# SCH_HACK-HOLIDAY_2025-01-30.net
KiCad netlist of a schematic drawn in EasyEDA
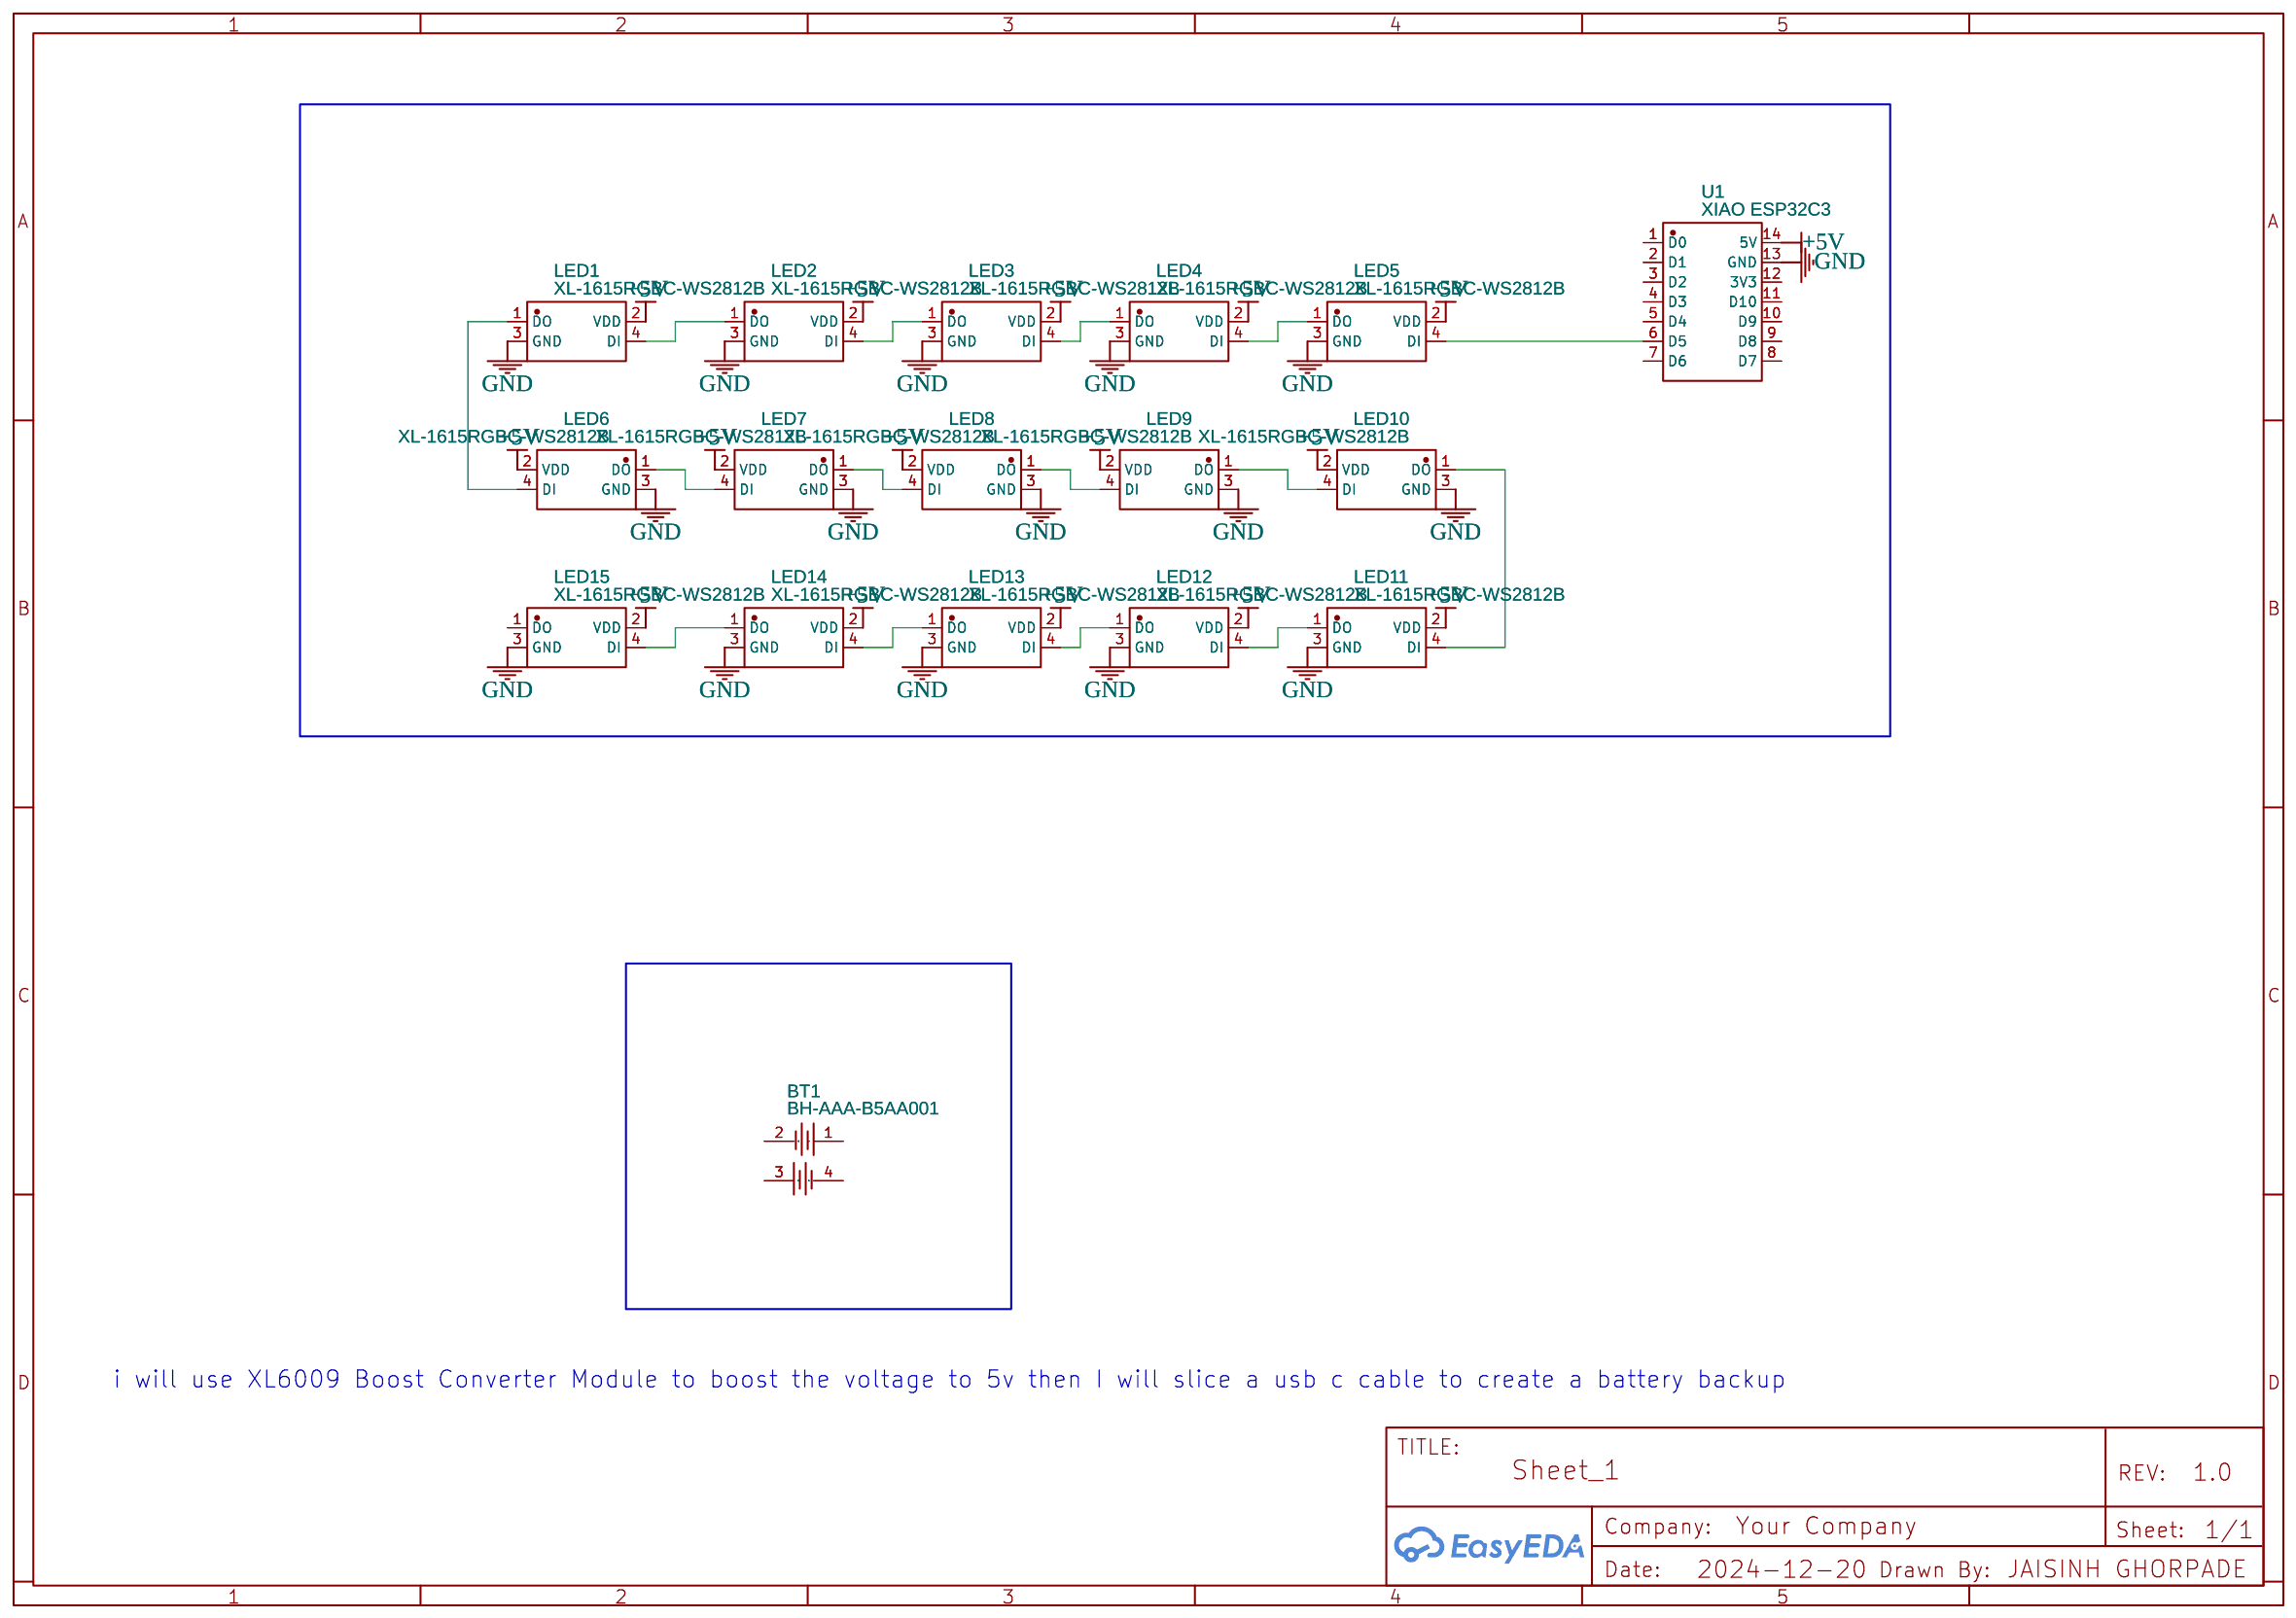
[diagram p0: schematic sheet]

(export (version "E")
  (design (tool "Eeschema 10.0.6"))
  (components
    (comp (ref "BT1")
      (value "BH-AAA-B5AA001")
      (fields (field (name "Manufacturer") "MYOUNG(美阳)"))
      (libsource (lib "") (part "BH-AAA-B5AA001"))
    )
    (comp (ref "LED1")
      (value "XL-1615RGBC-WS2812B")
      (fields (field (name "Manufacturer") "XINGLIGHT(成兴光)"))
      (libsource (lib "") (part "XL-1615RGBC-WS2812B"))
    )
    (comp (ref "LED2")
      (value "XL-1615RGBC-WS2812B")
      (fields (field (name "Manufacturer") "XINGLIGHT(成兴光)"))
      (libsource (lib "") (part "XL-1615RGBC-WS2812B"))
    )
    (comp (ref "LED3")
      (value "XL-1615RGBC-WS2812B")
      (fields (field (name "Manufacturer") "XINGLIGHT(成兴光)"))
      (libsource (lib "") (part "XL-1615RGBC-WS2812B"))
    )
    (comp (ref "LED4")
      (value "XL-1615RGBC-WS2812B")
      (fields (field (name "Manufacturer") "XINGLIGHT(成兴光)"))
      (libsource (lib "") (part "XL-1615RGBC-WS2812B"))
    )
    (comp (ref "LED5")
      (value "XL-1615RGBC-WS2812B")
      (fields (field (name "Manufacturer") "XINGLIGHT(成兴光)"))
      (libsource (lib "") (part "XL-1615RGBC-WS2812B"))
    )
    (comp (ref "LED6")
      (value "XL-1615RGBC-WS2812B")
      (fields (field (name "Manufacturer") "XINGLIGHT(成兴光)"))
      (libsource (lib "") (part "XL-1615RGBC-WS2812B_1"))
    )
    (comp (ref "LED7")
      (value "XL-1615RGBC-WS2812B")
      (fields (field (name "Manufacturer") "XINGLIGHT(成兴光)"))
      (libsource (lib "") (part "XL-1615RGBC-WS2812B_1"))
    )
    (comp (ref "LED8")
      (value "XL-1615RGBC-WS2812B")
      (fields (field (name "Manufacturer") "XINGLIGHT(成兴光)"))
      (libsource (lib "") (part "XL-1615RGBC-WS2812B_1"))
    )
    (comp (ref "LED9")
      (value "XL-1615RGBC-WS2812B")
      (fields (field (name "Manufacturer") "XINGLIGHT(成兴光)"))
      (libsource (lib "") (part "XL-1615RGBC-WS2812B_1"))
    )
    (comp (ref "LED10")
      (value "XL-1615RGBC-WS2812B")
      (fields (field (name "Manufacturer") "XINGLIGHT(成兴光)"))
      (libsource (lib "") (part "XL-1615RGBC-WS2812B_1"))
    )
    (comp (ref "LED11")
      (value "XL-1615RGBC-WS2812B")
      (fields (field (name "Manufacturer") "XINGLIGHT(成兴光)"))
      (libsource (lib "") (part "XL-1615RGBC-WS2812B"))
    )
    (comp (ref "LED12")
      (value "XL-1615RGBC-WS2812B")
      (fields (field (name "Manufacturer") "XINGLIGHT(成兴光)"))
      (libsource (lib "") (part "XL-1615RGBC-WS2812B"))
    )
    (comp (ref "LED13")
      (value "XL-1615RGBC-WS2812B")
      (fields (field (name "Manufacturer") "XINGLIGHT(成兴光)"))
      (libsource (lib "") (part "XL-1615RGBC-WS2812B"))
    )
    (comp (ref "LED14")
      (value "XL-1615RGBC-WS2812B")
      (fields (field (name "Manufacturer") "XINGLIGHT(成兴光)"))
      (libsource (lib "") (part "XL-1615RGBC-WS2812B"))
    )
    (comp (ref "LED15")
      (value "XL-1615RGBC-WS2812B")
      (fields (field (name "Manufacturer") "XINGLIGHT(成兴光)"))
      (libsource (lib "") (part "XL-1615RGBC-WS2812B"))
    )
    (comp (ref "U1") (value "XIAO ESP32C3") (libsource (lib "") (part "XIAO ESP32C3")))
  )
  (nets
    (net (code "1") (name "+5V") (class "Default")
      (node (ref "LED1") (pin "2") (pinfunction "VDD_2") (pintype "unspecified"))
      (node (ref "LED10") (pin "2") (pinfunction "VDD_2") (pintype "unspecified"))
      (node (ref "LED11") (pin "2") (pinfunction "VDD_2") (pintype "unspecified"))
      (node (ref "LED12") (pin "2") (pinfunction "VDD_2") (pintype "unspecified"))
      (node (ref "LED13") (pin "2") (pinfunction "VDD_2") (pintype "unspecified"))
      (node (ref "LED14") (pin "2") (pinfunction "VDD_2") (pintype "unspecified"))
      (node (ref "LED15") (pin "2") (pinfunction "VDD_2") (pintype "unspecified"))
      (node (ref "LED2") (pin "2") (pinfunction "VDD_2") (pintype "unspecified"))
      (node (ref "LED3") (pin "2") (pinfunction "VDD_2") (pintype "unspecified"))
      (node (ref "LED4") (pin "2") (pinfunction "VDD_2") (pintype "unspecified"))
      (node (ref "LED5") (pin "2") (pinfunction "VDD_2") (pintype "unspecified"))
      (node (ref "LED6") (pin "2") (pinfunction "VDD_2") (pintype "unspecified"))
      (node (ref "LED7") (pin "2") (pinfunction "VDD_2") (pintype "unspecified"))
      (node (ref "LED8") (pin "2") (pinfunction "VDD_2") (pintype "unspecified"))
      (node (ref "LED9") (pin "2") (pinfunction "VDD_2") (pintype "unspecified"))
      (node (ref "U1") (pin "14") (pinfunction "5V_14") (pintype "unspecified"))
    )
    (net (code "2") (name "GND") (class "Default")
      (node (ref "LED1") (pin "3") (pinfunction "GND_3") (pintype "unspecified"))
      (node (ref "LED10") (pin "3") (pinfunction "GND_3") (pintype "unspecified"))
      (node (ref "LED11") (pin "3") (pinfunction "GND_3") (pintype "unspecified"))
      (node (ref "LED12") (pin "3") (pinfunction "GND_3") (pintype "unspecified"))
      (node (ref "LED13") (pin "3") (pinfunction "GND_3") (pintype "unspecified"))
      (node (ref "LED14") (pin "3") (pinfunction "GND_3") (pintype "unspecified"))
      (node (ref "LED15") (pin "3") (pinfunction "GND_3") (pintype "unspecified"))
      (node (ref "LED2") (pin "3") (pinfunction "GND_3") (pintype "unspecified"))
      (node (ref "LED3") (pin "3") (pinfunction "GND_3") (pintype "unspecified"))
      (node (ref "LED4") (pin "3") (pinfunction "GND_3") (pintype "unspecified"))
      (node (ref "LED5") (pin "3") (pinfunction "GND_3") (pintype "unspecified"))
      (node (ref "LED6") (pin "3") (pinfunction "GND_3") (pintype "unspecified"))
      (node (ref "LED7") (pin "3") (pinfunction "GND_3") (pintype "unspecified"))
      (node (ref "LED8") (pin "3") (pinfunction "GND_3") (pintype "unspecified"))
      (node (ref "LED9") (pin "3") (pinfunction "GND_3") (pintype "unspecified"))
      (node (ref "U1") (pin "13") (pinfunction "GND_13") (pintype "unspecified"))
    )
    (net (code "3") (name "Net-(LED1-DI)") (class "Default")
      (node (ref "LED1") (pin "4") (pinfunction "DI_4") (pintype "unspecified"))
      (node (ref "LED2") (pin "1") (pinfunction "DO_1") (pintype "unspecified"))
    )
    (net (code "4") (name "Net-(LED1-DO)") (class "Default")
      (node (ref "LED1") (pin "1") (pinfunction "DO_1") (pintype "unspecified"))
      (node (ref "LED6") (pin "4") (pinfunction "DI_4") (pintype "unspecified"))
    )
    (net (code "5") (name "Net-(LED2-DI)") (class "Default")
      (node (ref "LED2") (pin "4") (pinfunction "DI_4") (pintype "unspecified"))
      (node (ref "LED3") (pin "1") (pinfunction "DO_1") (pintype "unspecified"))
    )
    (net (code "6") (name "Net-(LED3-DI)") (class "Default")
      (node (ref "LED3") (pin "4") (pinfunction "DI_4") (pintype "unspecified"))
      (node (ref "LED4") (pin "1") (pinfunction "DO_1") (pintype "unspecified"))
    )
    (net (code "7") (name "Net-(LED4-DI)") (class "Default")
      (node (ref "LED4") (pin "4") (pinfunction "DI_4") (pintype "unspecified"))
      (node (ref "LED5") (pin "1") (pinfunction "DO_1") (pintype "unspecified"))
    )
    (net (code "8") (name "Net-(LED5-DI)") (class "Default")
      (node (ref "LED5") (pin "4") (pinfunction "DI_4") (pintype "unspecified"))
      (node (ref "U1") (pin "6") (pinfunction "D5_6") (pintype "unspecified"))
    )
    (net (code "9") (name "Net-(LED6-DO)") (class "Default")
      (node (ref "LED6") (pin "1") (pinfunction "DO_1") (pintype "unspecified"))
      (node (ref "LED7") (pin "4") (pinfunction "DI_4") (pintype "unspecified"))
    )
    (net (code "10") (name "Net-(LED7-DO)") (class "Default")
      (node (ref "LED7") (pin "1") (pinfunction "DO_1") (pintype "unspecified"))
      (node (ref "LED8") (pin "4") (pinfunction "DI_4") (pintype "unspecified"))
    )
    (net (code "11") (name "Net-(LED8-DO)") (class "Default")
      (node (ref "LED8") (pin "1") (pinfunction "DO_1") (pintype "unspecified"))
      (node (ref "LED9") (pin "4") (pinfunction "DI_4") (pintype "unspecified"))
    )
    (net (code "12") (name "Net-(LED10-DI)") (class "Default")
      (node (ref "LED10") (pin "4") (pinfunction "DI_4") (pintype "unspecified"))
      (node (ref "LED9") (pin "1") (pinfunction "DO_1") (pintype "unspecified"))
    )
    (net (code "13") (name "Net-(LED10-DO)") (class "Default")
      (node (ref "LED10") (pin "1") (pinfunction "DO_1") (pintype "unspecified"))
      (node (ref "LED11") (pin "4") (pinfunction "DI_4") (pintype "unspecified"))
    )
    (net (code "14") (name "Net-(LED11-DO)") (class "Default")
      (node (ref "LED11") (pin "1") (pinfunction "DO_1") (pintype "unspecified"))
      (node (ref "LED12") (pin "4") (pinfunction "DI_4") (pintype "unspecified"))
    )
    (net (code "15") (name "Net-(LED12-DO)") (class "Default")
      (node (ref "LED12") (pin "1") (pinfunction "DO_1") (pintype "unspecified"))
      (node (ref "LED13") (pin "4") (pinfunction "DI_4") (pintype "unspecified"))
    )
    (net (code "16") (name "Net-(LED13-DO)") (class "Default")
      (node (ref "LED13") (pin "1") (pinfunction "DO_1") (pintype "unspecified"))
      (node (ref "LED14") (pin "4") (pinfunction "DI_4") (pintype "unspecified"))
    )
    (net (code "17") (name "Net-(LED14-DO)") (class "Default")
      (node (ref "LED14") (pin "1") (pinfunction "DO_1") (pintype "unspecified"))
      (node (ref "LED15") (pin "4") (pinfunction "DI_4") (pintype "unspecified"))
    )
    (net (code "18") (name "unconnected-(BT1-Pad1)") (class "Default")
      (node (ref "BT1") (pin "1") (pinfunction "1_1") (pintype "input"))
    )
    (net (code "19") (name "unconnected-(BT1-Pad2)") (class "Default")
      (node (ref "BT1") (pin "2") (pinfunction "2_2") (pintype "input"))
    )
    (net (code "20") (name "unconnected-(BT1-Pad3)") (class "Default")
      (node (ref "BT1") (pin "3") (pinfunction "3_3") (pintype "input"))
    )
    (net (code "21") (name "unconnected-(BT1-Pad4)") (class "Default")
      (node (ref "BT1") (pin "4") (pinfunction "4_4") (pintype "input"))
    )
    (net (code "22") (name "unconnected-(LED15-DO-Pad1)") (class "Default")
      (node (ref "LED15") (pin "1") (pinfunction "DO_1") (pintype "unspecified"))
    )
    (net (code "23") (name "unconnected-(U1-3V3-Pad12)") (class "Default")
      (node (ref "U1") (pin "12") (pinfunction "3V3_12") (pintype "unspecified"))
    )
    (net (code "24") (name "unconnected-(U1-D0-Pad1)") (class "Default")
      (node (ref "U1") (pin "1") (pinfunction "D0_1") (pintype "unspecified"))
    )
    (net (code "25") (name "unconnected-(U1-D1-Pad2)") (class "Default")
      (node (ref "U1") (pin "2") (pinfunction "D1_2") (pintype "unspecified"))
    )
    (net (code "26") (name "unconnected-(U1-D2-Pad3)") (class "Default")
      (node (ref "U1") (pin "3") (pinfunction "D2_3") (pintype "unspecified"))
    )
    (net (code "27") (name "unconnected-(U1-D3-Pad4)") (class "Default")
      (node (ref "U1") (pin "4") (pinfunction "D3_4") (pintype "unspecified"))
    )
    (net (code "28") (name "unconnected-(U1-D4-Pad5)") (class "Default")
      (node (ref "U1") (pin "5") (pinfunction "D4_5") (pintype "unspecified"))
    )
    (net (code "29") (name "unconnected-(U1-D6-Pad7)") (class "Default")
      (node (ref "U1") (pin "7") (pinfunction "D6_7") (pintype "unspecified"))
    )
    (net (code "30") (name "unconnected-(U1-D7-Pad8)") (class "Default")
      (node (ref "U1") (pin "8") (pinfunction "D7_8") (pintype "unspecified"))
    )
    (net (code "31") (name "unconnected-(U1-D8-Pad9)") (class "Default")
      (node (ref "U1") (pin "9") (pinfunction "D8_9") (pintype "unspecified"))
    )
    (net (code "32") (name "unconnected-(U1-D9-Pad10)") (class "Default")
      (node (ref "U1") (pin "10") (pinfunction "D9_10") (pintype "unspecified"))
    )
    (net (code "33") (name "unconnected-(U1-D10-Pad11)") (class "Default")
      (node (ref "U1") (pin "11") (pinfunction "D10_11") (pintype "unspecified"))
    )
  )
)
